# BW1098OBC_IMX378.net
KiCad netlist of a schematic drawn in Altium Designer
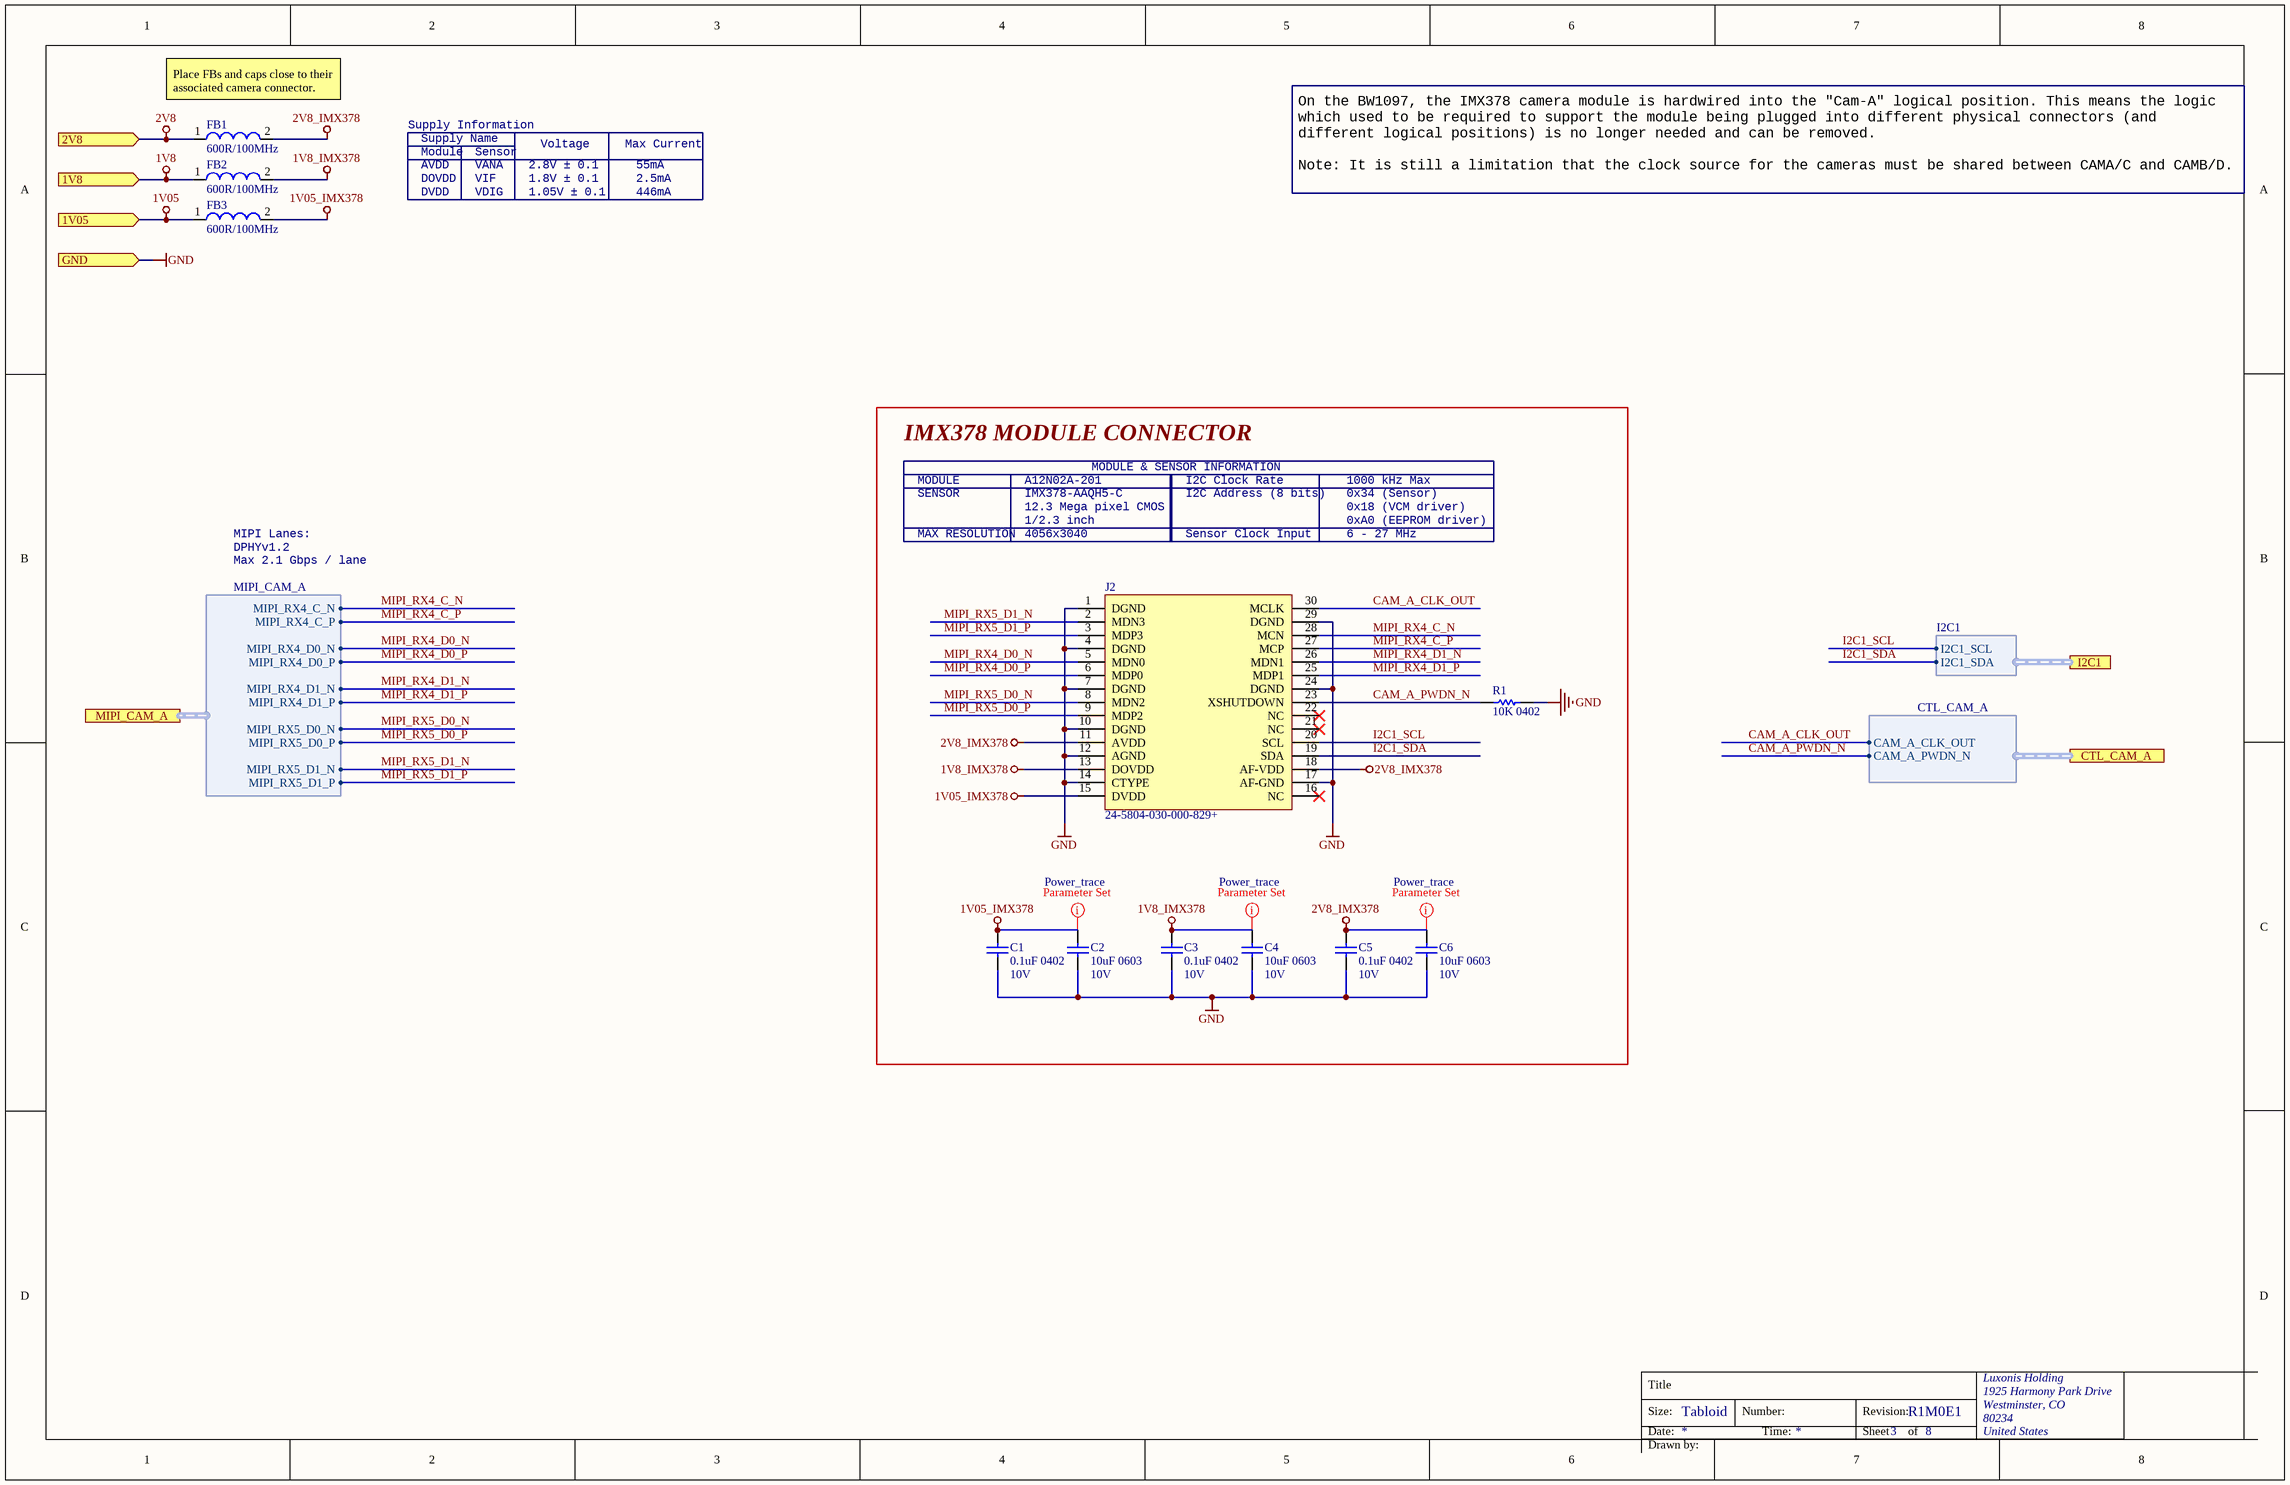
[diagram p0: BW1098OBC_IMX378.SchDoc]

(export (version "E")
  (design (tool "Eeschema 10.0.6"))
  (components
    (comp (ref "C1")
      (value "0.1uF 0402")
      (footprint "CAP_Altium_Vault_Generic:CAPC0402(1005)70_L")
      (description "CAP CER 0.1UF 10V X7R 0402 5%")
      (fields (field (name "TOLERANCE") "5%") (field (name "VOLTAGE RATING") "10V"))
      (libsource (lib "LuxonisMaster") (part "GRM155R71A104JA01D"))
    )
    (comp (ref "C2")
      (value "10uF 0603")
      (footprint "CAP_Altium_Vault_Generic:CAPC0603(1608)100_L")
      (description "CAP CER 10UF 10V X5R 0603 20%")
      (fields (field (name "TOLERANCE") "20%") (field (name "VOLTAGE RATING") "10V"))
      (libsource (lib "LuxonisMaster") (part "GRM188R61A106ME69D"))
    )
    (comp (ref "C3")
      (value "0.1uF 0402")
      (footprint "CAP_Altium_Vault_Generic:CAPC0402(1005)70_L")
      (description "CAP CER 0.1UF 10V X7R 0402 5%")
      (fields (field (name "TOLERANCE") "5%") (field (name "VOLTAGE RATING") "10V"))
      (libsource (lib "LuxonisMaster") (part "GRM155R71A104JA01D"))
    )
    (comp (ref "C4")
      (value "10uF 0603")
      (footprint "CAP_Altium_Vault_Generic:CAPC0603(1608)100_L")
      (description "CAP CER 10UF 10V X5R 0603 20%")
      (fields (field (name "TOLERANCE") "20%") (field (name "VOLTAGE RATING") "10V"))
      (libsource (lib "LuxonisMaster") (part "GRM188R61A106ME69D"))
    )
    (comp (ref "C5")
      (value "0.1uF 0402")
      (footprint "CAP_Altium_Vault_Generic:CAPC0402(1005)70_L")
      (description "CAP CER 0.1UF 10V X7R 0402 5%")
      (fields (field (name "TOLERANCE") "5%") (field (name "VOLTAGE RATING") "10V"))
      (libsource (lib "LuxonisMaster") (part "GRM155R71A104JA01D"))
    )
    (comp (ref "C6")
      (value "10uF 0603")
      (footprint "CAP_Altium_Vault_Generic:CAPC0603(1608)100_L")
      (description "CAP CER 10UF 10V X5R 0603 20%")
      (fields (field (name "TOLERANCE") "20%") (field (name "VOLTAGE RATING") "10V"))
      (libsource (lib "LuxonisMaster") (part "GRM188R61A106ME69D"))
    )
    (comp (ref "FB1")
      (value "600R/100MHz")
      (footprint "LuxonisMaster:2508056017Y2")
      (description "FERRITE BEAD, 0.1OHM, 2A, 0805, 600R/100MHz")
      (fields (field (name "TOLERANCE") "25%"))
      (libsource (lib "LuxonisMaster") (part "2508056017Y2"))
    )
    (comp (ref "FB2")
      (value "600R/100MHz")
      (footprint "LuxonisMaster:2508056017Y2")
      (description "FERRITE BEAD, 0.1OHM, 2A, 0805, 600R/100MHz")
      (fields (field (name "TOLERANCE") "25%"))
      (libsource (lib "LuxonisMaster") (part "2508056017Y2"))
    )
    (comp (ref "FB3")
      (value "600R/100MHz")
      (footprint "LuxonisMaster:2508056017Y2")
      (description "FERRITE BEAD, 0.1OHM, 2A, 0805, 600R/100MHz")
      (fields (field (name "TOLERANCE") "25%"))
      (libsource (lib "LuxonisMaster") (part "2508056017Y2"))
    )
    (comp (ref "J2")
      (value "24-5804-030-000-829+")
      (footprint "LuxonisMaster:A12N02A-201")
      (description "CONN Series 5804 board to board 0.4mm pitch 30 way connector")
      (libsource (lib "LuxonisMaster") (part "A12N02A-201_Connector"))
    )
    (comp (ref "R1")
      (value "10K 0402")
      (footprint "RES_Altium_Vault_Generic:RESC0402(1005)_L")
      (fields (field (name "TOLERANCE") "1%"))
      (libsource (lib "LuxonisMaster") (part "RC0402FR-1310KL"))
    )
  )
  (nets
    (net (code "4") (name "/CAM_A_CLK_OUT") (class "Default")
      (node (ref "J2") (pin "30") (pinfunction "MCLK_30") (pintype "passive"))
    )
    (net (code "5") (name "/CAM_A_PWDN_N") (class "Default")
      (node (ref "J2") (pin "23") (pinfunction "XSHUTDOWN_23") (pintype "passive"))
      (node (ref "R1") (pin "1") (pinfunction "1_1") (pintype "passive"))
    )
    (net (code "6") (name "/I2C1_SCL") (class "Default")
      (node (ref "J2") (pin "20") (pinfunction "SCL_20") (pintype "passive"))
    )
    (net (code "7") (name "/I2C1_SDA") (class "Default")
      (node (ref "J2") (pin "19") (pinfunction "SDA_19") (pintype "passive"))
    )
    (net (code "8") (name "/MIPI_RX4_C_N") (class "Default")
      (node (ref "J2") (pin "28") (pinfunction "MCN_28") (pintype "passive"))
    )
    (net (code "9") (name "/MIPI_RX4_C_P") (class "Default")
      (node (ref "J2") (pin "27") (pinfunction "MCP_27") (pintype "passive"))
    )
    (net (code "10") (name "/MIPI_RX4_D0_N") (class "Default")
      (node (ref "J2") (pin "5") (pinfunction "MDN0_5") (pintype "passive"))
    )
    (net (code "11") (name "/MIPI_RX4_D0_P") (class "Default")
      (node (ref "J2") (pin "6") (pinfunction "MDP0_6") (pintype "passive"))
    )
    (net (code "12") (name "/MIPI_RX4_D1_N") (class "Default")
      (node (ref "J2") (pin "26") (pinfunction "MDN1_26") (pintype "passive"))
    )
    (net (code "13") (name "/MIPI_RX4_D1_P") (class "Default")
      (node (ref "J2") (pin "25") (pinfunction "MDP1_25") (pintype "passive"))
    )
    (net (code "14") (name "/MIPI_RX5_D0_N") (class "Default")
      (node (ref "J2") (pin "8") (pinfunction "MDN2_8") (pintype "passive"))
    )
    (net (code "15") (name "/MIPI_RX5_D0_P") (class "Default")
      (node (ref "J2") (pin "9") (pinfunction "MDP2_9") (pintype "passive"))
    )
    (net (code "16") (name "/MIPI_RX5_D1_N") (class "Default")
      (node (ref "J2") (pin "2") (pinfunction "MDN3_2") (pintype "passive"))
    )
    (net (code "17") (name "/MIPI_RX5_D1_P") (class "Default")
      (node (ref "J2") (pin "3") (pinfunction "MDP3_3") (pintype "passive"))
    )
    (net (code "21") (name "1V05") (class "Default")
      (node (ref "FB3") (pin "1") (pinfunction "1_1") (pintype "passive"))
    )
    (net (code "22") (name "1V05_IMX378") (class "Default")
      (node (ref "C1") (pin "2") (pinfunction "2_2") (pintype "passive"))
      (node (ref "C2") (pin "2") (pinfunction "2_2") (pintype "passive"))
      (node (ref "FB3") (pin "2") (pinfunction "2_2") (pintype "passive"))
      (node (ref "J2") (pin "15") (pinfunction "DVDD_15") (pintype "passive"))
    )
    (net (code "23") (name "1V8") (class "Default")
      (node (ref "FB2") (pin "1") (pinfunction "1_1") (pintype "passive"))
    )
    (net (code "24") (name "1V8_IMX378") (class "Default")
      (node (ref "C3") (pin "2") (pinfunction "2_2") (pintype "passive"))
      (node (ref "C4") (pin "2") (pinfunction "2_2") (pintype "passive"))
      (node (ref "FB2") (pin "2") (pinfunction "2_2") (pintype "passive"))
      (node (ref "J2") (pin "13") (pinfunction "DOVDD_13") (pintype "passive"))
    )
    (net (code "25") (name "2V8") (class "Default")
      (node (ref "FB1") (pin "1") (pinfunction "1_1") (pintype "passive"))
    )
    (net (code "26") (name "2V8_IMX378") (class "Default")
      (node (ref "C5") (pin "2") (pinfunction "2_2") (pintype "passive"))
      (node (ref "C6") (pin "2") (pinfunction "2_2") (pintype "passive"))
      (node (ref "FB1") (pin "2") (pinfunction "2_2") (pintype "passive"))
      (node (ref "J2") (pin "11") (pinfunction "AVDD_11") (pintype "passive"))
      (node (ref "J2") (pin "18") (pinfunction "AF-VDD_18") (pintype "passive"))
    )
    (net (code "27") (name "GND") (class "Default")
      (node (ref "C1") (pin "1") (pinfunction "1_1") (pintype "passive"))
      (node (ref "C2") (pin "1") (pinfunction "1_1") (pintype "passive"))
      (node (ref "C3") (pin "1") (pinfunction "1_1") (pintype "passive"))
      (node (ref "C4") (pin "1") (pinfunction "1_1") (pintype "passive"))
      (node (ref "C5") (pin "1") (pinfunction "1_1") (pintype "passive"))
      (node (ref "C6") (pin "1") (pinfunction "1_1") (pintype "passive"))
      (node (ref "J2") (pin "1") (pinfunction "DGND_1") (pintype "passive"))
      (node (ref "J2") (pin "10") (pinfunction "DGND_10") (pintype "passive"))
      (node (ref "J2") (pin "12") (pinfunction "AGND_12") (pintype "passive"))
      (node (ref "J2") (pin "14") (pinfunction "CTYPE_14") (pintype "passive"))
      (node (ref "J2") (pin "17") (pinfunction "AF-GND_17") (pintype "passive"))
      (node (ref "J2") (pin "24") (pinfunction "DGND_24") (pintype "passive"))
      (node (ref "J2") (pin "29") (pinfunction "DGND_29") (pintype "passive"))
      (node (ref "J2") (pin "4") (pinfunction "DGND_4") (pintype "passive"))
      (node (ref "J2") (pin "7") (pinfunction "DGND_7") (pintype "passive"))
      (node (ref "R1") (pin "2") (pinfunction "2_2") (pintype "passive"))
    )
    (net (code "28") (name "unconnected-(J2-NC-Pad16)") (class "Default")
      (node (ref "J2") (pin "16") (pinfunction "NC_16") (pintype "passive+no_connect"))
    )
    (net (code "29") (name "unconnected-(J2-NC-Pad21)") (class "Default")
      (node (ref "J2") (pin "21") (pinfunction "NC_21") (pintype "passive+no_connect"))
    )
    (net (code "30") (name "unconnected-(J2-NC-Pad22)") (class "Default")
      (node (ref "J2") (pin "22") (pinfunction "NC_22") (pintype "passive+no_connect"))
    )
  )
)
